# LaunchPadFlightController_Schematic.net
KiCad netlist of a schematic drawn in EAGLE
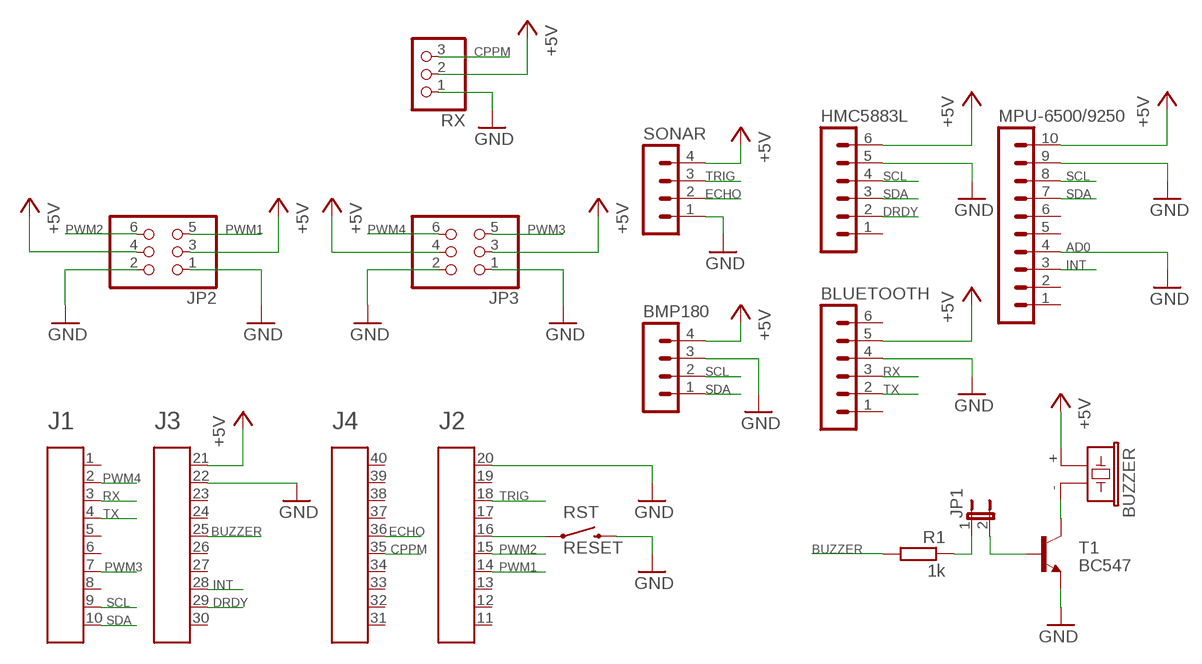
[diagram p0: schematic, sheet 1]

(export (version "E")
  (design (tool "Eeschema 10.0.6"))
  (components
    (comp (ref "A1")
      (value "HEADER4X10-BOOSTERPACK")
      (footprint "eagle-import:4X10-BOOSTERPACK")
      (libsource (lib "eagle-import") (part "HEADER4X10-BOOSTERPACK"))
    )
    (comp (ref "BLUETOOTH")
      (value "MA06-1")
      (footprint "eagle-import:MA06-1")
      (libsource (lib "eagle-import") (part "MA06-1"))
    )
    (comp (ref "BMP180")
      (value "MA04-1")
      (footprint "eagle-import:MA04-1")
      (libsource (lib "eagle-import") (part "MA04-1"))
    )
    (comp (ref "BUZZER")
      (value "F/CM12P")
      (footprint "eagle-import:F_CM12P")
      (libsource (lib "eagle-import") (part "F/CM12P"))
    )
    (comp (ref "HMC5883L")
      (value "MA06-1")
      (footprint "eagle-import:MA06-1")
      (libsource (lib "eagle-import") (part "MA06-1"))
    )
    (comp (ref "JP1")
      (value "JP1E")
      (footprint "eagle-import:JP1")
      (libsource (lib "eagle-import") (part "JP1E"))
    )
    (comp (ref "JP2")
      (value "PINHD-2X3")
      (footprint "eagle-import:2X03")
      (libsource (lib "eagle-import") (part "PINHD-2X3"))
    )
    (comp (ref "JP3")
      (value "PINHD-2X3")
      (footprint "eagle-import:2X03")
      (libsource (lib "eagle-import") (part "PINHD-2X3"))
    )
    (comp (ref "MPU-6500/9250")
      (value "MA10-1")
      (footprint "eagle-import:MA10-1")
      (libsource (lib "eagle-import") (part "MA10-1"))
    )
    (comp (ref "R1")
      (value "1k")
      (footprint "eagle-import:0207_10")
      (libsource (lib "eagle-import") (part "R-EU_0207/10"))
    )
    (comp (ref "RST")
      (value "RESET")
      (footprint "eagle-import:TACTILE-PTH-EZ")
      (libsource (lib "eagle-import") (part "SWITCHES_PTH_EZ"))
    )
    (comp (ref "RX")
      (value "PINHD-1X3")
      (footprint "eagle-import:1X03")
      (libsource (lib "eagle-import") (part "PINHD-1X3"))
    )
    (comp (ref "SONAR")
      (value "MA04-1")
      (footprint "eagle-import:MA04-1")
      (libsource (lib "eagle-import") (part "MA04-1"))
    )
    (comp (ref "T1")
      (value "BC547")
      (footprint "eagle-import:TO92")
      (libsource (lib "eagle-import") (part "BC547"))
    )
  )
  (nets
    (net (code "1") (name "+5V") (class "Default")
      (node (ref "A1") (pin "21") (pinfunction "P$21_21") (pintype "bidirectional"))
      (node (ref "BLUETOOTH") (pin "5") (pinfunction "5_5") (pintype "passive"))
      (node (ref "BMP180") (pin "4") (pinfunction "4_4") (pintype "passive"))
      (node (ref "BUZZER") (pin "+") (pinfunction "1_+") (pintype "passive"))
      (node (ref "HMC5883L") (pin "6") (pinfunction "6_6") (pintype "passive"))
      (node (ref "JP2") (pin "3") (pinfunction "3_3") (pintype "passive"))
      (node (ref "JP2") (pin "4") (pinfunction "4_4") (pintype "passive"))
      (node (ref "JP3") (pin "3") (pinfunction "3_3") (pintype "passive"))
      (node (ref "JP3") (pin "4") (pinfunction "4_4") (pintype "passive"))
      (node (ref "MPU-6500/9250") (pin "10") (pinfunction "10_10") (pintype "passive"))
      (node (ref "RX") (pin "2") (pinfunction "2_2") (pintype "passive"))
      (node (ref "SONAR") (pin "4") (pinfunction "4_4") (pintype "passive"))
    )
    (net (code "2") (name "/BUZZER") (class "Default")
      (node (ref "A1") (pin "25") (pinfunction "P$25_25") (pintype "bidirectional"))
      (node (ref "R1") (pin "2") (pinfunction "2_2") (pintype "passive"))
    )
    (net (code "3") (name "/CPPM") (class "Default")
      (node (ref "A1") (pin "35") (pinfunction "P$35_35") (pintype "bidirectional"))
      (node (ref "RX") (pin "3") (pinfunction "3_3") (pintype "passive"))
    )
    (net (code "4") (name "/DRDY") (class "Default")
      (node (ref "A1") (pin "29") (pinfunction "P$29_29") (pintype "bidirectional"))
      (node (ref "HMC5883L") (pin "2") (pinfunction "2_2") (pintype "passive"))
    )
    (net (code "5") (name "/ECHO") (class "Default")
      (node (ref "A1") (pin "36") (pinfunction "P$36_36") (pintype "bidirectional"))
      (node (ref "SONAR") (pin "2") (pinfunction "2_2") (pintype "passive"))
    )
    (net (code "6") (name "/INT") (class "Default")
      (node (ref "A1") (pin "28") (pinfunction "P$28_28") (pintype "bidirectional"))
      (node (ref "MPU-6500/9250") (pin "3") (pinfunction "3_3") (pintype "passive"))
    )
    (net (code "7") (name "/PWM1") (class "Default")
      (node (ref "A1") (pin "14") (pinfunction "P$14_14") (pintype "bidirectional"))
      (node (ref "JP2") (pin "5") (pinfunction "5_5") (pintype "passive"))
    )
    (net (code "8") (name "/PWM2") (class "Default")
      (node (ref "A1") (pin "15") (pinfunction "P$15_15") (pintype "bidirectional"))
      (node (ref "JP2") (pin "6") (pinfunction "6_6") (pintype "passive"))
    )
    (net (code "9") (name "/PWM3") (class "Default")
      (node (ref "A1") (pin "7") (pinfunction "P$7_7") (pintype "bidirectional"))
      (node (ref "JP3") (pin "5") (pinfunction "5_5") (pintype "passive"))
    )
    (net (code "10") (name "/PWM4") (class "Default")
      (node (ref "A1") (pin "2") (pinfunction "P$2_2") (pintype "bidirectional"))
      (node (ref "JP3") (pin "6") (pinfunction "6_6") (pintype "passive"))
    )
    (net (code "11") (name "/RX") (class "Default")
      (node (ref "A1") (pin "3") (pinfunction "P$3_3") (pintype "bidirectional"))
      (node (ref "BLUETOOTH") (pin "3") (pinfunction "3_3") (pintype "passive"))
    )
    (net (code "12") (name "/SCL") (class "Default")
      (node (ref "A1") (pin "9") (pinfunction "P$9_9") (pintype "bidirectional"))
      (node (ref "BMP180") (pin "2") (pinfunction "2_2") (pintype "passive"))
      (node (ref "HMC5883L") (pin "4") (pinfunction "4_4") (pintype "passive"))
      (node (ref "MPU-6500/9250") (pin "8") (pinfunction "8_8") (pintype "passive"))
    )
    (net (code "13") (name "/SDA") (class "Default")
      (node (ref "A1") (pin "10") (pinfunction "P$10_10") (pintype "bidirectional"))
      (node (ref "BMP180") (pin "1") (pinfunction "1_1") (pintype "passive"))
      (node (ref "HMC5883L") (pin "3") (pinfunction "3_3") (pintype "passive"))
      (node (ref "MPU-6500/9250") (pin "7") (pinfunction "7_7") (pintype "passive"))
    )
    (net (code "14") (name "/TRIG") (class "Default")
      (node (ref "A1") (pin "18") (pinfunction "P$18_18") (pintype "bidirectional"))
      (node (ref "SONAR") (pin "3") (pinfunction "3_3") (pintype "passive"))
    )
    (net (code "15") (name "/TX") (class "Default")
      (node (ref "A1") (pin "4") (pinfunction "P$4_4") (pintype "bidirectional"))
      (node (ref "BLUETOOTH") (pin "2") (pinfunction "2_2") (pintype "passive"))
    )
    (net (code "16") (name "GND") (class "Default")
      (node (ref "A1") (pin "20") (pinfunction "P$20_20") (pintype "bidirectional"))
      (node (ref "A1") (pin "22") (pinfunction "P$22_22") (pintype "bidirectional"))
      (node (ref "BLUETOOTH") (pin "4") (pinfunction "4_4") (pintype "passive"))
      (node (ref "BMP180") (pin "3") (pinfunction "3_3") (pintype "passive"))
      (node (ref "HMC5883L") (pin "5") (pinfunction "5_5") (pintype "passive"))
      (node (ref "JP2") (pin "1") (pinfunction "1_1") (pintype "passive"))
      (node (ref "JP2") (pin "2") (pinfunction "2_2") (pintype "passive"))
      (node (ref "JP3") (pin "1") (pinfunction "1_1") (pintype "passive"))
      (node (ref "JP3") (pin "2") (pinfunction "2_2") (pintype "passive"))
      (node (ref "MPU-6500/9250") (pin "4") (pinfunction "4_4") (pintype "passive"))
      (node (ref "MPU-6500/9250") (pin "9") (pinfunction "9_9") (pintype "passive"))
      (node (ref "RST") (pin "3") (pinfunction "2_3") (pintype "passive"))
      (node (ref "RX") (pin "1") (pinfunction "1_1") (pintype "passive"))
      (node (ref "SONAR") (pin "1") (pinfunction "1_1") (pintype "passive"))
      (node (ref "T1") (pin "1") (pinfunction "E_1") (pintype "passive"))
    )
    (net (code "17") (name "Net-(A1-P$16)") (class "Default")
      (node (ref "A1") (pin "16") (pinfunction "P$16_16") (pintype "bidirectional"))
      (node (ref "RST") (pin "1") (pinfunction "1_1") (pintype "passive"))
    )
    (net (code "18") (name "Net-(BUZZER-2)") (class "Default")
      (node (ref "BUZZER") (pin "-") (pinfunction "2_-") (pintype "passive"))
      (node (ref "T1") (pin "3") (pinfunction "C_3") (pintype "passive"))
    )
    (net (code "19") (name "Net-(JP1-Pad1)") (class "Default")
      (node (ref "JP1") (pin "1") (pinfunction "1_1") (pintype "passive"))
      (node (ref "R1") (pin "1") (pinfunction "1_1") (pintype "passive"))
    )
    (net (code "20") (name "Net-(T1-B)") (class "Default")
      (node (ref "JP1") (pin "2") (pinfunction "2_2") (pintype "passive"))
      (node (ref "T1") (pin "2") (pinfunction "B_2") (pintype "passive"))
    )
    (net (code "21") (name "unconnected-(A1-P$1-Pad1)") (class "Default")
      (node (ref "A1") (pin "1") (pinfunction "P$1_1") (pintype "bidirectional"))
    )
    (net (code "22") (name "unconnected-(A1-P$5-Pad5)") (class "Default")
      (node (ref "A1") (pin "5") (pinfunction "P$5_5") (pintype "bidirectional"))
    )
    (net (code "23") (name "unconnected-(A1-P$6-Pad6)") (class "Default")
      (node (ref "A1") (pin "6") (pinfunction "P$6_6") (pintype "bidirectional"))
    )
    (net (code "24") (name "unconnected-(A1-P$8-Pad8)") (class "Default")
      (node (ref "A1") (pin "8") (pinfunction "P$8_8") (pintype "bidirectional"))
    )
    (net (code "25") (name "unconnected-(A1-P$11-Pad11)") (class "Default")
      (node (ref "A1") (pin "11") (pinfunction "P$11_11") (pintype "bidirectional"))
    )
    (net (code "26") (name "unconnected-(A1-P$12-Pad12)") (class "Default")
      (node (ref "A1") (pin "12") (pinfunction "P$12_12") (pintype "bidirectional"))
    )
    (net (code "27") (name "unconnected-(A1-P$13-Pad13)") (class "Default")
      (node (ref "A1") (pin "13") (pinfunction "P$13_13") (pintype "bidirectional"))
    )
    (net (code "28") (name "unconnected-(A1-P$17-Pad17)") (class "Default")
      (node (ref "A1") (pin "17") (pinfunction "P$17_17") (pintype "bidirectional"))
    )
    (net (code "29") (name "unconnected-(A1-P$19-Pad19)") (class "Default")
      (node (ref "A1") (pin "19") (pinfunction "P$19_19") (pintype "bidirectional"))
    )
    (net (code "30") (name "unconnected-(A1-P$23-Pad23)") (class "Default")
      (node (ref "A1") (pin "23") (pinfunction "P$23_23") (pintype "bidirectional"))
    )
    (net (code "31") (name "unconnected-(A1-P$24-Pad24)") (class "Default")
      (node (ref "A1") (pin "24") (pinfunction "P$24_24") (pintype "bidirectional"))
    )
    (net (code "32") (name "unconnected-(A1-P$26-Pad26)") (class "Default")
      (node (ref "A1") (pin "26") (pinfunction "P$26_26") (pintype "bidirectional"))
    )
    (net (code "33") (name "unconnected-(A1-P$27-Pad27)") (class "Default")
      (node (ref "A1") (pin "27") (pinfunction "P$27_27") (pintype "bidirectional"))
    )
    (net (code "34") (name "unconnected-(A1-P$30-Pad30)") (class "Default")
      (node (ref "A1") (pin "30") (pinfunction "P$30_30") (pintype "bidirectional"))
    )
    (net (code "35") (name "unconnected-(A1-P$31-Pad31)") (class "Default")
      (node (ref "A1") (pin "31") (pinfunction "P$31_31") (pintype "bidirectional"))
    )
    (net (code "36") (name "unconnected-(A1-P$32-Pad32)") (class "Default")
      (node (ref "A1") (pin "32") (pinfunction "P$32_32") (pintype "bidirectional"))
    )
    (net (code "37") (name "unconnected-(A1-P$33-Pad33)") (class "Default")
      (node (ref "A1") (pin "33") (pinfunction "P$33_33") (pintype "bidirectional"))
    )
    (net (code "38") (name "unconnected-(A1-P$34-Pad34)") (class "Default")
      (node (ref "A1") (pin "34") (pinfunction "P$34_34") (pintype "bidirectional"))
    )
    (net (code "39") (name "unconnected-(A1-P$37-Pad37)") (class "Default")
      (node (ref "A1") (pin "37") (pinfunction "P$37_37") (pintype "bidirectional"))
    )
    (net (code "40") (name "unconnected-(A1-P$38-Pad38)") (class "Default")
      (node (ref "A1") (pin "38") (pinfunction "P$38_38") (pintype "bidirectional"))
    )
    (net (code "41") (name "unconnected-(A1-P$39-Pad39)") (class "Default")
      (node (ref "A1") (pin "39") (pinfunction "P$39_39") (pintype "bidirectional"))
    )
    (net (code "42") (name "unconnected-(A1-P$40-Pad40)") (class "Default")
      (node (ref "A1") (pin "40") (pinfunction "P$40_40") (pintype "bidirectional"))
    )
    (net (code "43") (name "unconnected-(BLUETOOTH-Pad1)") (class "Default")
      (node (ref "BLUETOOTH") (pin "1") (pinfunction "1_1") (pintype "passive"))
    )
    (net (code "44") (name "unconnected-(BLUETOOTH-Pad6)") (class "Default")
      (node (ref "BLUETOOTH") (pin "6") (pinfunction "6_6") (pintype "passive"))
    )
    (net (code "45") (name "unconnected-(HMC5883L-Pad1)") (class "Default")
      (node (ref "HMC5883L") (pin "1") (pinfunction "1_1") (pintype "passive"))
    )
    (net (code "46") (name "unconnected-(MPU-6500/9250-Pad1)") (class "Default")
      (node (ref "MPU-6500/9250") (pin "1") (pinfunction "1_1") (pintype "passive"))
    )
    (net (code "47") (name "unconnected-(MPU-6500/9250-Pad2)") (class "Default")
      (node (ref "MPU-6500/9250") (pin "2") (pinfunction "2_2") (pintype "passive"))
    )
    (net (code "48") (name "unconnected-(MPU-6500/9250-Pad5)") (class "Default")
      (node (ref "MPU-6500/9250") (pin "5") (pinfunction "5_5") (pintype "passive"))
    )
    (net (code "49") (name "unconnected-(MPU-6500/9250-Pad6)") (class "Default")
      (node (ref "MPU-6500/9250") (pin "6") (pinfunction "6_6") (pintype "passive"))
    )
  )
)
